# Motor_control.net
KiCad netlist of a schematic drawn in Altium Designer
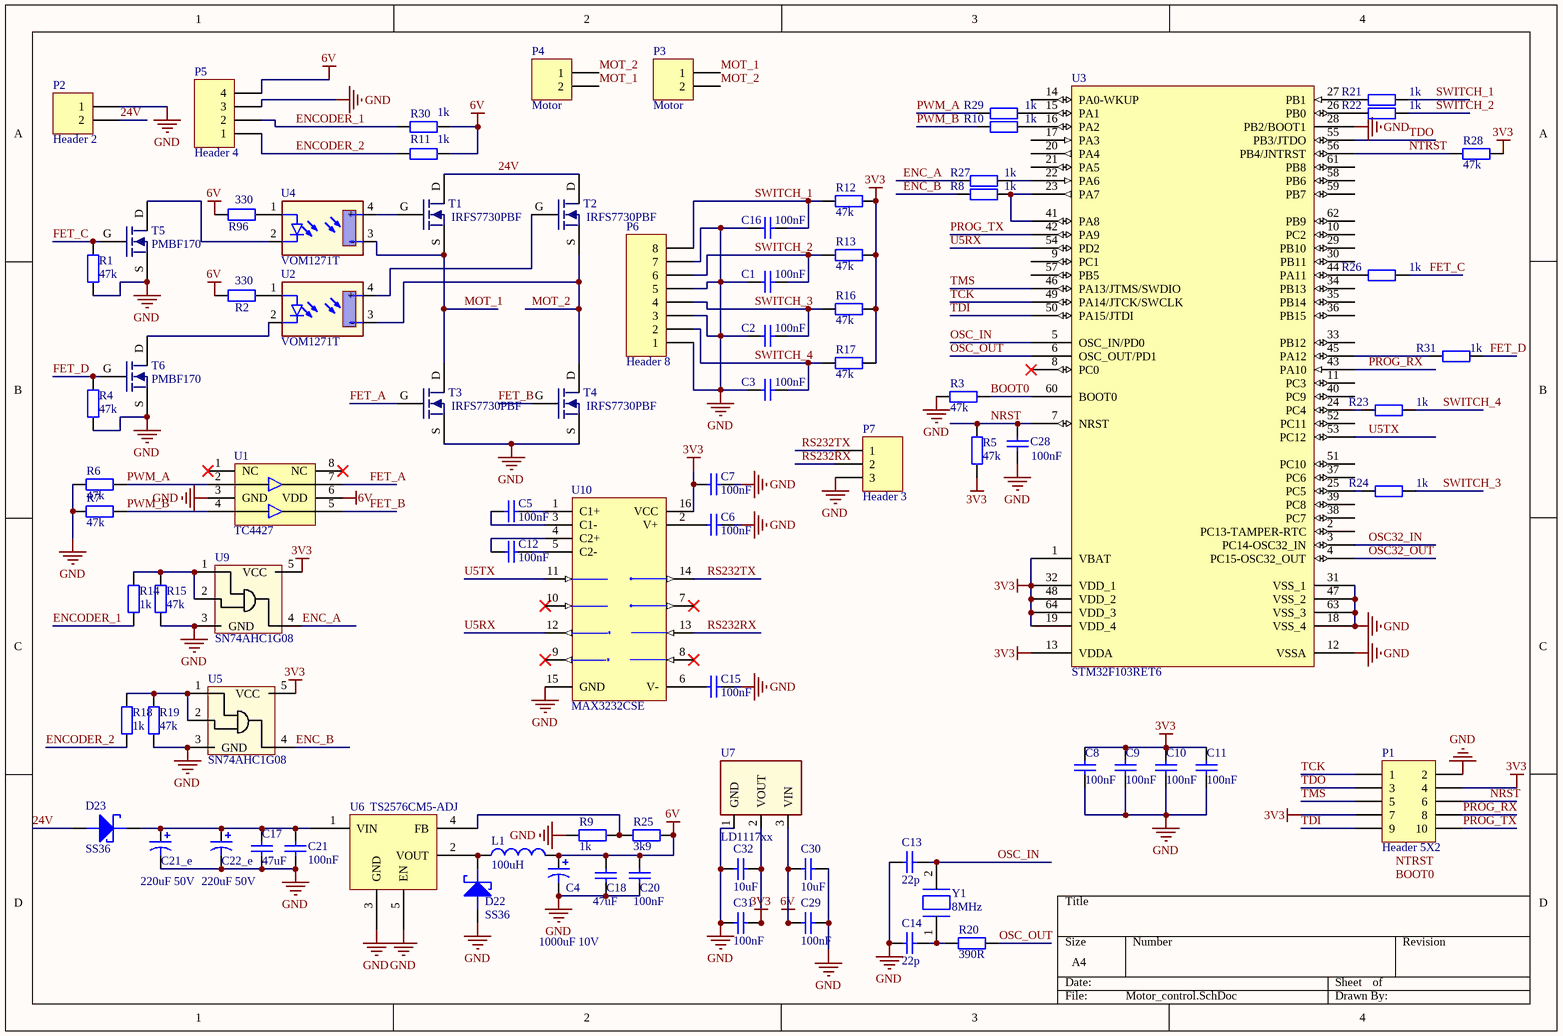
[diagram p0: Motor_control.SchDoc]

(export (version "E")
  (design (tool "Eeschema 10.0.6"))
  (components
    (comp (ref "C1")
      (value "100nF")
      (footprint "FP_0603_CAP_080")
      (description "Capacitor")
      (fields (field (name "VOLTAGE") "50V"))
      (libsource (lib "Miscellaneous Devices") (part "Cap"))
    )
    (comp (ref "C2")
      (value "100nF")
      (footprint "FP_0603_CAP_080")
      (description "Capacitor")
      (fields (field (name "VOLTAGE") "50V"))
      (libsource (lib "Miscellaneous Devices") (part "Cap"))
    )
    (comp (ref "C3")
      (value "100nF")
      (footprint "FP_0603_CAP_080")
      (description "Capacitor")
      (fields (field (name "VOLTAGE") "50V"))
      (libsource (lib "Miscellaneous Devices") (part "Cap"))
    )
    (comp (ref "C4")
      (value "1000uF 10V")
      (footprint "CAP_ALU_ELKO_10D_10,5H")
      (description "Polarized Capacitor (Radial)")
      (libsource (lib "Miscellaneous Devices") (part "Cap Pol1"))
    )
    (comp (ref "C5")
      (value "100nF")
      (footprint "FP_0603_CAP_080")
      (description "Capacitor")
      (libsource (lib "Capacitor") (part "CAP"))
    )
    (comp (ref "C6")
      (value "100nF")
      (footprint "FP_0603_CAP_080")
      (description "Capacitor")
      (libsource (lib "Capacitor") (part "CAP"))
    )
    (comp (ref "C7")
      (value "100nF")
      (footprint "FP_0603_CAP_080")
      (description "Capacitor")
      (libsource (lib "Capacitor") (part "CAP"))
    )
    (comp (ref "C8")
      (value "100nF")
      (footprint "FP_0603_CAP_080")
      (description "Capacitor")
      (libsource (lib "Capacitor") (part "CAP"))
    )
    (comp (ref "C9")
      (value "100nF")
      (footprint "FP_0603_CAP_080")
      (description "Capacitor")
      (libsource (lib "Capacitor") (part "CAP"))
    )
    (comp (ref "C10")
      (value "100nF")
      (footprint "FP_0603_CAP_080")
      (description "Capacitor")
      (libsource (lib "Capacitor") (part "CAP"))
    )
    (comp (ref "C11")
      (value "100nF")
      (footprint "FP_0603_CAP_080")
      (description "Capacitor")
      (libsource (lib "Capacitor") (part "CAP"))
    )
    (comp (ref "C12")
      (value "100nF")
      (footprint "FP_0603_CAP_080")
      (description "Capacitor")
      (libsource (lib "Capacitor") (part "CAP"))
    )
    (comp (ref "C13")
      (value "22p")
      (footprint "FP_0603_CAP_080")
      (description "Capacitor")
      (fields (field (name "PUBLISHER") "Altium Limited"))
      (libsource (lib "Miscellaneous Devices") (part "Cap"))
    )
    (comp (ref "C14")
      (value "22p")
      (footprint "FP_0603_CAP_080")
      (description "Capacitor")
      (fields (field (name "PUBLISHER") "Altium Limited"))
      (libsource (lib "Miscellaneous Devices") (part "Cap"))
    )
    (comp (ref "C15")
      (value "100nF")
      (footprint "FP_0603_CAP_080")
      (description "Capacitor")
      (libsource (lib "Capacitor") (part "CAP"))
    )
    (comp (ref "C16")
      (value "100nF")
      (footprint "FP_0603_CAP_080")
      (description "Capacitor")
      (fields (field (name "VOLTAGE") "50V"))
      (libsource (lib "Miscellaneous Devices") (part "Cap"))
    )
    (comp (ref "C17")
      (value "47uF")
      (footprint "FP_1206_CAP_125")
      (description "Capacitor")
      (libsource (lib "Miscellaneous Devices") (part "Cap"))
    )
    (comp (ref "C18")
      (value "47uF")
      (footprint "FP_1206_CAP_125")
      (description "Capacitor")
      (libsource (lib "Miscellaneous Devices") (part "Cap"))
    )
    (comp (ref "C20")
      (value "100nF")
      (footprint "FP_0603_CAP_080")
      (description "Capacitor")
      (libsource (lib "Miscellaneous Devices") (part "Cap"))
    )
    (comp (ref "C21")
      (value "100nF")
      (footprint "FP_0603_CAP_080")
      (description "Capacitor")
      (libsource (lib "Miscellaneous Devices") (part "Cap"))
    )
    (comp (ref "C21_e")
      (value "220uF 50V")
      (footprint "CAP_ALU_ELKO_10D_10,5H")
      (description "Polarized Capacitor (Radial)")
      (libsource (lib "Miscellaneous Devices") (part "Cap Pol1"))
    )
    (comp (ref "C22_e")
      (value "220uF 50V")
      (footprint "CAP_ALU_ELKO_10D_10,5H")
      (description "Polarized Capacitor (Radial)")
      (libsource (lib "Miscellaneous Devices") (part "Cap Pol1"))
    )
    (comp (ref "C28")
      (value "100nF")
      (footprint "FP_0603_CAP_080")
      (description "Capacitor")
      (libsource (lib "Miscellaneous Devices") (part "Cap"))
    )
    (comp (ref "C29")
      (value "100nF")
      (footprint "FP_0603_CAP_080")
      (description "Capacitor")
      (fields (field (name "PUBLISHER") "Altium Limited"))
      (libsource (lib "Miscellaneous Devices") (part "Cap"))
    )
    (comp (ref "C30")
      (value "10uF")
      (footprint "FP_1206_CAP_085")
      (description "Capacitor")
      (fields (field (name "PUBLISHER") "Altium Limited"))
      (libsource (lib "Miscellaneous Devices") (part "Cap"))
    )
    (comp (ref "C31")
      (value "100nF")
      (footprint "FP_0603_CAP_080")
      (description "Capacitor")
      (fields (field (name "PUBLISHER") "Altium Limited"))
      (libsource (lib "Miscellaneous Devices") (part "Cap"))
    )
    (comp (ref "C32")
      (value "10uF")
      (footprint "FP_1206_CAP_085")
      (description "Capacitor")
      (fields (field (name "PUBLISHER") "Altium Limited"))
      (libsource (lib "Miscellaneous Devices") (part "Cap"))
    )
    (comp (ref "D22")
      (value "SS36")
      (footprint "DIODE_SMC")
      (description "NXP - PMEG3020EJ,115 - SCHOTTKY RECT 30V 2A SOD323F")
      (libsource (lib "Diode") (part "SCHOTTKY"))
    )
    (comp (ref "D23")
      (value "SS36")
      (footprint "DIODE_SMC")
      (description "NXP - PMEG3020EJ,115 - SCHOTTKY RECT 30V 2A SOD323F")
      (libsource (lib "Diode") (part "SCHOTTKY"))
    )
    (comp (ref "L1")
      (value "100uH")
      (footprint "SRR1206_T")
      (description "Inductor")
      (fields (field (name "PUBLISHER") "Altium Limited"))
      (libsource (lib "Miscellaneous Devices") (part "Inductor"))
    )
    (comp (ref "P1")
      (value "Header 5X2")
      (footprint "HEADER_10_BOX")
      (description "Header, 5-Pin, Dual row")
      (fields (field (name "PUBLISHER") "Altium Limited"))
      (libsource (lib "EtherIOv2") (part "Header 5X2"))
    )
    (comp (ref "P2")
      (value "Header 2")
      (footprint "Sorkapocs 2P 5mm")
      (description "Header, 2-Pin")
      (libsource (lib "Miscellaneous Connectors") (part "Header 2"))
    )
    (comp (ref "P3")
      (value "Motor")
      (footprint "Sorkapocs 2P 5mm")
      (description "Header, 2-Pin")
      (libsource (lib "Miscellaneous Connectors") (part "Header 2"))
    )
    (comp (ref "P4")
      (value "Motor")
      (footprint "3.96mm 2P  90° NCW396-02R")
      (description "Header, 2-Pin")
      (libsource (lib "Miscellaneous Connectors") (part "Header 2"))
    )
    (comp (ref "P5")
      (value "Header 4")
      (footprint "jst-s4b-xh-a")
      (description "Header, 4-Pin")
      (libsource (lib "Miscellaneous Connectors") (part "Header 4"))
    )
    (comp (ref "P6")
      (value "Header 8")
      (footprint "Sorkapocs 8P 5mm")
      (description "Header, 8-Pin")
      (libsource (lib "Miscellaneous Connectors") (part "Header 8"))
    )
    (comp (ref "P7")
      (value "Header 3")
      (footprint "Sorkapocs 3P 5mm")
      (description "Header, 3-Pin")
      (libsource (lib "Miscellaneous Connectors") (part "Header 3"))
    )
    (comp (ref "R1")
      (value "47k")
      (footprint "FP_0603_RES")
      (description "Resistor")
      (libsource (lib "Miscellaneous Devices") (part "Res3"))
    )
    (comp (ref "R2")
      (value "330")
      (footprint "FP_0603_RES")
      (description "Resistor")
      (libsource (lib "") (part "Res3_2"))
    )
    (comp (ref "R3")
      (value "47k")
      (footprint "FP_0603_RES")
      (description "Resistor")
      (libsource (lib "") (part "Res3_1"))
    )
    (comp (ref "R4")
      (value "47k")
      (footprint "FP_0603_RES")
      (description "Resistor")
      (libsource (lib "Miscellaneous Devices") (part "Res3"))
    )
    (comp (ref "R5")
      (value "47k")
      (footprint "FP_0603_RES")
      (description "Resistor")
      (libsource (lib "Miscellaneous Devices") (part "Res3"))
    )
    (comp (ref "R6")
      (value "47k")
      (footprint "FP_0603_RES")
      (description "Resistor")
      (libsource (lib "") (part "Res3_1"))
    )
    (comp (ref "R7")
      (value "47k")
      (footprint "FP_0603_RES")
      (description "Resistor")
      (libsource (lib "") (part "Res3_1"))
    )
    (comp (ref "R8")
      (value "1k")
      (footprint "FP_0603_RES")
      (description "Resistor")
      (libsource (lib "") (part "Res3_1"))
    )
    (comp (ref "R9")
      (value "1k")
      (footprint "FP_0603_RES")
      (description "Resistor")
      (libsource (lib "") (part "Res3_1"))
    )
    (comp (ref "R10")
      (value "1k")
      (footprint "FP_0603_RES")
      (description "Resistor")
      (libsource (lib "") (part "Res3_1"))
    )
    (comp (ref "R11")
      (value "1k")
      (footprint "FP_0603_RES")
      (description "Resistor")
      (libsource (lib "") (part "Res3_1"))
    )
    (comp (ref "R12")
      (value "47k")
      (footprint "FP_0603_RES")
      (description "Resistor")
      (libsource (lib "") (part "Res3_1"))
    )
    (comp (ref "R13")
      (value "47k")
      (footprint "FP_0603_RES")
      (description "Resistor")
      (libsource (lib "") (part "Res3_1"))
    )
    (comp (ref "R14")
      (value "1k")
      (footprint "FP_0603_RES")
      (description "Resistor")
      (libsource (lib "Miscellaneous Devices") (part "Res3"))
    )
    (comp (ref "R15")
      (value "47k")
      (footprint "FP_0603_RES")
      (description "Resistor")
      (libsource (lib "Miscellaneous Devices") (part "Res3"))
    )
    (comp (ref "R16")
      (value "47k")
      (footprint "FP_0603_RES")
      (description "Resistor")
      (libsource (lib "") (part "Res3_1"))
    )
    (comp (ref "R17")
      (value "47k")
      (footprint "FP_0603_RES")
      (description "Resistor")
      (libsource (lib "") (part "Res3_1"))
    )
    (comp (ref "R18")
      (value "1k")
      (footprint "FP_0603_RES")
      (description "Resistor")
      (libsource (lib "Miscellaneous Devices") (part "Res3"))
    )
    (comp (ref "R19")
      (value "47k")
      (footprint "FP_0603_RES")
      (description "Resistor")
      (libsource (lib "Miscellaneous Devices") (part "Res3"))
    )
    (comp (ref "R20")
      (value "390R")
      (footprint "FP_0603_RES")
      (description "Resistor")
      (libsource (lib "Resistor") (part "RES"))
    )
    (comp (ref "R21")
      (value "1k")
      (footprint "FP_0603_RES")
      (description "Resistor")
      (libsource (lib "") (part "Res3_1"))
    )
    (comp (ref "R22")
      (value "1k")
      (footprint "FP_0603_RES")
      (description "Resistor")
      (libsource (lib "") (part "Res3_1"))
    )
    (comp (ref "R23")
      (value "1k")
      (footprint "FP_0603_RES")
      (description "Resistor")
      (libsource (lib "") (part "Res3_1"))
    )
    (comp (ref "R24")
      (value "1k")
      (footprint "FP_0603_RES")
      (description "Resistor")
      (libsource (lib "") (part "Res3_1"))
    )
    (comp (ref "R25")
      (value "3k9")
      (footprint "FP_0603_RES")
      (description "Resistor")
      (libsource (lib "") (part "Res3_2"))
    )
    (comp (ref "R26")
      (value "1k")
      (footprint "FP_0603_RES")
      (description "Resistor")
      (libsource (lib "") (part "Res3_1"))
    )
    (comp (ref "R27")
      (value "1k")
      (footprint "FP_0603_RES")
      (description "Resistor")
      (libsource (lib "") (part "Res3_1"))
    )
    (comp (ref "R28")
      (value "47k")
      (footprint "FP_0603_RES")
      (description "Resistor")
      (libsource (lib "") (part "Res3_1"))
    )
    (comp (ref "R29")
      (value "1k")
      (footprint "FP_0603_RES")
      (description "Resistor")
      (libsource (lib "") (part "Res3_1"))
    )
    (comp (ref "R30")
      (value "1k")
      (footprint "FP_0603_RES")
      (description "Resistor")
      (libsource (lib "") (part "Res3_1"))
    )
    (comp (ref "R31")
      (value "1k")
      (footprint "FP_0603_RES")
      (description "Resistor")
      (libsource (lib "") (part "Res3_1"))
    )
    (comp (ref "R96")
      (value "330")
      (footprint "FP_0603_RES")
      (description "Resistor")
      (libsource (lib "") (part "Res3_2"))
    )
    (comp (ref "T1") (value "IRFS7730PBF") (footprint "FET_D2-PAK_7") (libsource (lib "FET") (part "NMOS")))
    (comp (ref "T2") (value "IRFS7730PBF") (footprint "FET_D2-PAK_7") (libsource (lib "FET") (part "NMOS")))
    (comp (ref "T3") (value "IRFS7730PBF") (footprint "FET_D2-PAK_7") (libsource (lib "FET") (part "NMOS")))
    (comp (ref "T4") (value "IRFS7730PBF") (footprint "FET_D2-PAK_7") (libsource (lib "FET") (part "NMOS")))
    (comp (ref "T5") (value "PMBF170") (footprint "FET_SOT23") (libsource (lib "FET") (part "NMOS")))
    (comp (ref "T6") (value "PMBF170") (footprint "FET_SOT23") (libsource (lib "FET") (part "NMOS")))
    (comp (ref "U1")
      (value "TC4427")
      (footprint "DIGITAL_SOIC8")
      (description "1.5A Dual High-Speed Power MOSFET Driver")
      (libsource (lib "Analog") (part "TC4427"))
    )
    (comp (ref "U2")
      (value "VOM1271T")
      (footprint "OPTO_SOP-4")
      (description "Photodiode Output Optocouplers MOSFET DRVR ISOLATED SOP4")
      (libsource (lib "Led_optical") (part "VOM1271T"))
    )
    (comp (ref "U3")
      (value "STM32F103RET6")
      (footprint "LQFP64_N")
      (description "STM32 ARM-based 32-bit MCU with 256 Kbytes Flash, 64-pin LQFP, Industrial Temperature")
      (libsource (lib "ST Microcontroller 32-Bit STM32") (part "STM32F103RBT6"))
    )
    (comp (ref "U4")
      (value "VOM1271T")
      (footprint "OPTO_SOP-4")
      (description "Photodiode Output Optocouplers MOSFET DRVR ISOLATED SOP4")
      (libsource (lib "Led_optical") (part "VOM1271T"))
    )
    (comp (ref "U5")
      (value "SN74AHC1G08")
      (footprint "GATE_SOT23-5")
      (description "1x2-INPUT AND-GATE")
      (libsource (lib "Logic_gate") (part "SN74AHC1G08"))
    )
    (comp (ref "U6")
      (value "TS2576CM5-ADJ")
      (footprint "SUPPLY_TO-263 5")
      (description "Step Down DC-DC Converter")
      (libsource (lib "EtherIOv2") (part "TS2576"))
    )
    (comp (ref "U7")
      (value "LD1117xx")
      (footprint "SUPPLY_SOT223")
      (description "LD1117xx 3,3V lin reg")
      (libsource (lib "Supply") (part "LD1117xx"))
    )
    (comp (ref "U9")
      (value "SN74AHC1G08")
      (footprint "GATE_SOT23-5")
      (description "1x2-INPUT AND-GATE")
      (libsource (lib "Logic_gate") (part "SN74AHC1G08"))
    )
    (comp (ref "U10")
      (value "MAX3232CSE")
      (footprint "DIGITAL_SOIC16")
      (description "MAX3232CSE 3.3.V RS232 converter")
      (libsource (lib "Digital") (part "MAX3232CSE"))
    )
    (comp (ref "Y1")
      (value "8MHz")
      (footprint "FP_CRYSTAL_HC49_SMD")
      (description "Standard HC49 quartz")
      (fields (field (name "MANUFACTURER") "Siward") (field (name "Comment") "8MHz Quartz HC49"))
      (libsource (lib "Fufi_altium_lib") (part "XTAL HC49"))
    )
  )
  (nets
    (net (code "1") (name "/24V") (class "Default")
      (node (ref "D23") (pin "A") (pinfunction "A_A") (pintype "passive"))
      (node (ref "P2") (pin "2") (pinfunction "2_2") (pintype "passive"))
      (node (ref "T1") (pin "D") (pinfunction "D_D") (pintype "passive"))
      (node (ref "T2") (pin "D") (pinfunction "D_D") (pintype "passive"))
    )
    (net (code "2") (name "/BOOT0") (class "Default")
      (node (ref "R3") (pin "2") (pinfunction "2_2") (pintype "passive"))
      (node (ref "U3") (pin "60") (pinfunction "BOOT0_60") (pintype "passive"))
    )
    (net (code "3") (name "/ENCODER_1") (class "Default")
      (node (ref "P5") (pin "2") (pinfunction "2_2") (pintype "passive"))
      (node (ref "R14") (pin "2") (pinfunction "2_2") (pintype "passive"))
      (node (ref "R30") (pin "1") (pinfunction "1_1") (pintype "passive"))
    )
    (net (code "4") (name "/ENCODER_2") (class "Default")
      (node (ref "P5") (pin "1") (pinfunction "1_1") (pintype "passive"))
      (node (ref "R11") (pin "1") (pinfunction "1_1") (pintype "passive"))
      (node (ref "R18") (pin "2") (pinfunction "2_2") (pintype "passive"))
    )
    (net (code "5") (name "/ENC_A") (class "Default")
      (node (ref "R27") (pin "1") (pinfunction "1_1") (pintype "passive"))
      (node (ref "U9") (pin "4") (pinfunction "Y_4") (pintype "passive"))
    )
    (net (code "6") (name "/ENC_B") (class "Default")
      (node (ref "R8") (pin "1") (pinfunction "1_1") (pintype "passive"))
      (node (ref "U5") (pin "4") (pinfunction "Y_4") (pintype "passive"))
    )
    (net (code "7") (name "/FET_A") (class "Default")
      (node (ref "T3") (pin "G") (pinfunction "G_G") (pintype "passive"))
      (node (ref "U1") (pin "7") (pinfunction "~{OUTA}_7") (pintype "passive"))
    )
    (net (code "8") (name "/FET_B") (class "Default")
      (node (ref "T4") (pin "G") (pinfunction "G_G") (pintype "passive"))
      (node (ref "U1") (pin "5") (pinfunction "OUTB_5") (pintype "passive"))
    )
    (net (code "9") (name "/FET_C") (class "Default")
      (node (ref "R1") (pin "1") (pinfunction "1_1") (pintype "passive"))
      (node (ref "R26") (pin "2") (pinfunction "2_2") (pintype "passive"))
      (node (ref "T5") (pin "G") (pinfunction "G_G") (pintype "passive"))
    )
    (net (code "10") (name "/FET_D") (class "Default")
      (node (ref "R31") (pin "2") (pinfunction "2_2") (pintype "passive"))
      (node (ref "R4") (pin "1") (pinfunction "1_1") (pintype "passive"))
      (node (ref "T6") (pin "G") (pinfunction "G_G") (pintype "passive"))
    )
    (net (code "11") (name "/MOT_1") (class "Default")
      (node (ref "P3") (pin "1") (pinfunction "1_1") (pintype "passive"))
      (node (ref "P4") (pin "2") (pinfunction "2_2") (pintype "passive"))
      (node (ref "T1") (pin "S") (pinfunction "S_S") (pintype "passive"))
      (node (ref "T3") (pin "D") (pinfunction "D_D") (pintype "passive"))
      (node (ref "U4") (pin "3") (pinfunction "-_3") (pintype "passive"))
    )
    (net (code "12") (name "/MOT_2") (class "Default")
      (node (ref "P3") (pin "2") (pinfunction "2_2") (pintype "passive"))
      (node (ref "P4") (pin "1") (pinfunction "1_1") (pintype "passive"))
      (node (ref "T2") (pin "S") (pinfunction "S_S") (pintype "passive"))
      (node (ref "T4") (pin "D") (pinfunction "D_D") (pintype "passive"))
      (node (ref "U2") (pin "3") (pinfunction "-_3") (pintype "passive"))
    )
    (net (code "13") (name "/NRST") (class "Default")
      (node (ref "C28") (pin "1") (pinfunction "1_1") (pintype "passive"))
      (node (ref "P1") (pin "6") (pinfunction "6_6") (pintype "passive"))
      (node (ref "R5") (pin "1") (pinfunction "1_1") (pintype "passive"))
      (node (ref "U3") (pin "7") (pinfunction "NRST_7") (pintype "bidirectional"))
    )
    (net (code "14") (name "/NTRST") (class "Default")
      (node (ref "R28") (pin "1") (pinfunction "1_1") (pintype "passive"))
      (node (ref "U3") (pin "56") (pinfunction "PB4/JNTRST_56") (pintype "bidirectional"))
    )
    (net (code "15") (name "/OSC32_IN") (class "Default")
      (node (ref "U3") (pin "3") (pinfunction "PC14-OSC32_IN_3") (pintype "bidirectional"))
    )
    (net (code "16") (name "/OSC32_OUT") (class "Default")
      (node (ref "U3") (pin "4") (pinfunction "PC15-OSC32_OUT_4") (pintype "bidirectional"))
    )
    (net (code "17") (name "/OSC_IN") (class "Default")
      (node (ref "C13") (pin "2") (pinfunction "2_2") (pintype "passive"))
      (node (ref "U3") (pin "5") (pinfunction "OSC_IN/PD0_5") (pintype "passive"))
      (node (ref "Y1") (pin "2") (pinfunction "2_2") (pintype "passive"))
    )
    (net (code "18") (name "/OSC_OUT") (class "Default")
      (node (ref "R20") (pin "2") (pinfunction "2_2") (pintype "passive"))
      (node (ref "U3") (pin "6") (pinfunction "OSC_OUT/PD1_6") (pintype "passive"))
    )
    (net (code "19") (name "/PROG_RX") (class "Default")
      (node (ref "P1") (pin "8") (pinfunction "8_8") (pintype "passive"))
      (node (ref "U3") (pin "43") (pinfunction "PA10_43") (pintype "input"))
    )
    (net (code "20") (name "/PROG_TX") (class "Default")
      (node (ref "P1") (pin "10") (pinfunction "10_10") (pintype "passive"))
      (node (ref "U3") (pin "42") (pinfunction "PA9_42") (pintype "bidirectional"))
    )
    (net (code "21") (name "/PWM_A") (class "Default")
      (node (ref "R29") (pin "1") (pinfunction "1_1") (pintype "passive"))
      (node (ref "R6") (pin "2") (pinfunction "2_2") (pintype "passive"))
      (node (ref "U1") (pin "2") (pinfunction "INA_2") (pintype "passive"))
    )
    (net (code "22") (name "/PWM_B") (class "Default")
      (node (ref "R10") (pin "1") (pinfunction "1_1") (pintype "passive"))
      (node (ref "R7") (pin "2") (pinfunction "2_2") (pintype "passive"))
      (node (ref "U1") (pin "4") (pinfunction "INB_4") (pintype "passive"))
    )
    (net (code "23") (name "/RS232RX") (class "Default")
      (node (ref "P7") (pin "2") (pinfunction "2_2") (pintype "passive"))
      (node (ref "U10") (pin "13") (pinfunction "R1IN_13") (pintype "input"))
    )
    (net (code "24") (name "/RS232TX") (class "Default")
      (node (ref "P7") (pin "1") (pinfunction "1_1") (pintype "passive"))
      (node (ref "U10") (pin "14") (pinfunction "T1OUT_14") (pintype "output"))
    )
    (net (code "25") (name "/SWITCH_1") (class "Default")
      (node (ref "C16") (pin "2") (pinfunction "2_2") (pintype "passive"))
      (node (ref "P6") (pin "8") (pinfunction "8_8") (pintype "passive"))
      (node (ref "R12") (pin "1") (pinfunction "1_1") (pintype "passive"))
      (node (ref "R21") (pin "2") (pinfunction "2_2") (pintype "passive"))
    )
    (net (code "26") (name "/SWITCH_2") (class "Default")
      (node (ref "C1") (pin "2") (pinfunction "2_2") (pintype "passive"))
      (node (ref "P6") (pin "6") (pinfunction "6_6") (pintype "passive"))
      (node (ref "R13") (pin "1") (pinfunction "1_1") (pintype "passive"))
      (node (ref "R22") (pin "2") (pinfunction "2_2") (pintype "passive"))
    )
    (net (code "27") (name "/SWITCH_3") (class "Default")
      (node (ref "C2") (pin "2") (pinfunction "2_2") (pintype "passive"))
      (node (ref "P6") (pin "4") (pinfunction "4_4") (pintype "passive"))
      (node (ref "R16") (pin "1") (pinfunction "1_1") (pintype "passive"))
      (node (ref "R24") (pin "2") (pinfunction "2_2") (pintype "passive"))
    )
    (net (code "28") (name "/SWITCH_4") (class "Default")
      (node (ref "C3") (pin "2") (pinfunction "2_2") (pintype "passive"))
      (node (ref "P6") (pin "2") (pinfunction "2_2") (pintype "passive"))
      (node (ref "R17") (pin "1") (pinfunction "1_1") (pintype "passive"))
      (node (ref "R23") (pin "2") (pinfunction "2_2") (pintype "passive"))
    )
    (net (code "29") (name "/TCK") (class "Default")
      (node (ref "P1") (pin "1") (pinfunction "1_1") (pintype "passive"))
      (node (ref "U3") (pin "49") (pinfunction "PA14/JTCK/SWCLK_49") (pintype "bidirectional"))
    )
    (net (code "30") (name "/TDI") (class "Default")
      (node (ref "P1") (pin "9") (pinfunction "9_9") (pintype "passive"))
      (node (ref "U3") (pin "50") (pinfunction "PA15/JTDI_50") (pintype "bidirectional"))
    )
    (net (code "31") (name "/TDO") (class "Default")
      (node (ref "P1") (pin "3") (pinfunction "3_3") (pintype "passive"))
      (node (ref "U3") (pin "55") (pinfunction "PB3/JTDO_55") (pintype "bidirectional"))
    )
    (net (code "32") (name "/TMS") (class "Default")
      (node (ref "P1") (pin "5") (pinfunction "5_5") (pintype "passive"))
      (node (ref "U3") (pin "46") (pinfunction "PA13/JTMS/SWDIO_46") (pintype "bidirectional"))
    )
    (net (code "33") (name "/U5RX") (class "Default")
      (node (ref "U10") (pin "12") (pinfunction "R1OUT_12") (pintype "output"))
      (node (ref "U3") (pin "54") (pinfunction "PD2_54") (pintype "bidirectional"))
    )
    (net (code "34") (name "/U5TX") (class "Default")
      (node (ref "U10") (pin "11") (pinfunction "T1IN_11") (pintype "input"))
      (node (ref "U3") (pin "53") (pinfunction "PC12_53") (pintype "bidirectional"))
    )
    (net (code "35") (name "3V3") (class "Default")
      (node (ref "C10") (pin "2") (pinfunction "2_2") (pintype "passive"))
      (node (ref "C11") (pin "2") (pinfunction "2_2") (pintype "passive"))
      (node (ref "C31") (pin "1") (pinfunction "1_1") (pintype "passive"))
      (node (ref "C32") (pin "2") (pinfunction "2_2") (pintype "passive"))
      (node (ref "C7") (pin "2") (pinfunction "2_2") (pintype "passive"))
      (node (ref "C8") (pin "2") (pinfunction "2_2") (pintype "passive"))
      (node (ref "C9") (pin "2") (pinfunction "2_2") (pintype "passive"))
      (node (ref "P1") (pin "4") (pinfunction "4_4") (pintype "passive"))
      (node (ref "P1") (pin "7") (pinfunction "7_7") (pintype "passive"))
      (node (ref "R12") (pin "2") (pinfunction "2_2") (pintype "passive"))
      (node (ref "R13") (pin "2") (pinfunction "2_2") (pintype "passive"))
      (node (ref "R16") (pin "2") (pinfunction "2_2") (pintype "passive"))
      (node (ref "R17") (pin "2") (pinfunction "2_2") (pintype "passive"))
      (node (ref "R28") (pin "2") (pinfunction "2_2") (pintype "passive"))
      (node (ref "R5") (pin "2") (pinfunction "2_2") (pintype "passive"))
      (node (ref "U10") (pin "16") (pinfunction "VCC_16") (pintype "power_in"))
      (node (ref "U3") (pin "1") (pinfunction "VBAT_1") (pintype "power_in"))
      (node (ref "U3") (pin "13") (pinfunction "VDDA_13") (pintype "power_in"))
      (node (ref "U3") (pin "19") (pinfunction "VDD_4_19") (pintype "power_in"))
      (node (ref "U3") (pin "32") (pinfunction "VDD_1_32") (pintype "power_in"))
      (node (ref "U3") (pin "48") (pinfunction "VDD_2_48") (pintype "power_in"))
      (node (ref "U3") (pin "64") (pinfunction "VDD_3_64") (pintype "power_in"))
      (node (ref "U5") (pin "5") (pinfunction "VCC_5") (pintype "passive"))
      (node (ref "U7") (pin "2") (pinfunction "VOUT_2") (pintype "passive"))
      (node (ref "U9") (pin "5") (pinfunction "VCC_5") (pintype "passive"))
    )
    (net (code "36") (name "6V") (class "Default")
      (node (ref "C18") (pin "2") (pinfunction "2_2") (pintype "passive"))
      (node (ref "C20") (pin "1") (pinfunction "1_1") (pintype "passive"))
      (node (ref "C29") (pin "2") (pinfunction "2_2") (pintype "passive"))
      (node (ref "C30") (pin "1") (pinfunction "1_1") (pintype "passive"))
      (node (ref "C4") (pin "P") (pinfunction "1_P") (pintype "passive"))
      (node (ref "L1") (pin "2") (pinfunction "2_2") (pintype "passive"))
      (node (ref "P5") (pin "4") (pinfunction "4_4") (pintype "passive"))
      (node (ref "R11") (pin "2") (pinfunction "2_2") (pintype "passive"))
      (node (ref "R2") (pin "2") (pinfunction "2_2") (pintype "passive"))
      (node (ref "R25") (pin "1") (pinfunction "1_1") (pintype "passive"))
      (node (ref "R30") (pin "2") (pinfunction "2_2") (pintype "passive"))
      (node (ref "R96") (pin "2") (pinfunction "2_2") (pintype "passive"))
      (node (ref "U1") (pin "6") (pinfunction "VDD_6") (pintype "power_in"))
      (node (ref "U7") (pin "3") (pinfunction "VIN_3") (pintype "passive"))
    )
    (net (code "37") (name "GND") (class "Default")
      (node (ref "C1") (pin "1") (pinfunction "1_1") (pintype "passive"))
      (node (ref "C10") (pin "1") (pinfunction "1_1") (pintype "passive"))
      (node (ref "C11") (pin "1") (pinfunction "1_1") (pintype "passive"))
      (node (ref "C13") (pin "1") (pinfunction "1_1") (pintype "passive"))
      (node (ref "C14") (pin "2") (pinfunction "2_2") (pintype "passive"))
      (node (ref "C15") (pin "1") (pinfunction "1_1") (pintype "passive"))
      (node (ref "C16") (pin "1") (pinfunction "1_1") (pintype "passive"))
      (node (ref "C17") (pin "1") (pinfunction "1_1") (pintype "passive"))
      (node (ref "C18") (pin "1") (pinfunction "1_1") (pintype "passive"))
      (node (ref "C2") (pin "1") (pinfunction "1_1") (pintype "passive"))
      (node (ref "C20") (pin "2") (pinfunction "2_2") (pintype "passive"))
      (node (ref "C21") (pin "2") (pinfunction "2_2") (pintype "passive"))
      (node (ref "C21_e") (pin "N") (pinfunction "2_N") (pintype "passive"))
      (node (ref "C22_e") (pin "N") (pinfunction "2_N") (pintype "passive"))
      (node (ref "C28") (pin "2") (pinfunction "2_2") (pintype "passive"))
      (node (ref "C29") (pin "1") (pinfunction "1_1") (pintype "passive"))
      (node (ref "C3") (pin "1") (pinfunction "1_1") (pintype "passive"))
      (node (ref "C30") (pin "2") (pinfunction "2_2") (pintype "passive"))
      (node (ref "C31") (pin "2") (pinfunction "2_2") (pintype "passive"))
      (node (ref "C32") (pin "1") (pinfunction "1_1") (pintype "passive"))
      (node (ref "C4") (pin "N") (pinfunction "2_N") (pintype "passive"))
      (node (ref "C6") (pin "1") (pinfunction "1_1") (pintype "passive"))
      (node (ref "C7") (pin "1") (pinfunction "1_1") (pintype "passive"))
      (node (ref "C8") (pin "1") (pinfunction "1_1") (pintype "passive"))
      (node (ref "C9") (pin "1") (pinfunction "1_1") (pintype "passive"))
      (node (ref "D22") (pin "A") (pinfunction "A_A") (pintype "passive"))
      (node (ref "P1") (pin "2") (pinfunction "2_2") (pintype "passive"))
      (node (ref "P2") (pin "1") (pinfunction "1_1") (pintype "passive"))
      (node (ref "P5") (pin "3") (pinfunction "3_3") (pintype "passive"))
      (node (ref "P6") (pin "1") (pinfunction "1_1") (pintype "passive"))
      (node (ref "P6") (pin "3") (pinfunction "3_3") (pintype "passive"))
      (node (ref "P6") (pin "5") (pinfunction "5_5") (pintype "passive"))
      (node (ref "P6") (pin "7") (pinfunction "7_7") (pintype "passive"))
      (node (ref "P7") (pin "3") (pinfunction "3_3") (pintype "passive"))
      (node (ref "R1") (pin "2") (pinfunction "2_2") (pintype "passive"))
      (node (ref "R15") (pin "2") (pinfunction "2_2") (pintype "passive"))
      (node (ref "R19") (pin "2") (pinfunction "2_2") (pintype "passive"))
      (node (ref "R3") (pin "1") (pinfunction "1_1") (pintype "passive"))
      (node (ref "R4") (pin "2") (pinfunction "2_2") (pintype "passive"))
      (node (ref "R6") (pin "1") (pinfunction "1_1") (pintype "passive"))
      (node (ref "R7") (pin "1") (pinfunction "1_1") (pintype "passive"))
      (node (ref "R9") (pin "1") (pinfunction "1_1") (pintype "passive"))
      (node (ref "T3") (pin "S") (pinfunction "S_S") (pintype "passive"))
      (node (ref "T4") (pin "S") (pinfunction "S_S") (pintype "passive"))
      (node (ref "T5") (pin "S") (pinfunction "S_S") (pintype "passive"))
      (node (ref "T6") (pin "S") (pinfunction "S_S") (pintype "passive"))
      (node (ref "U1") (pin "3") (pinfunction "GND_3") (pintype "power_in"))
      (node (ref "U10") (pin "15") (pinfunction "GND_15") (pintype "power_in"))
      (node (ref "U3") (pin "12") (pinfunction "VSSA_12") (pintype "power_in"))
      (node (ref "U3") (pin "18") (pinfunction "VSS_4_18") (pintype "power_in"))
      (node (ref "U3") (pin "28") (pinfunction "PB2/BOOT1_28") (pintype "passive"))
      (node (ref "U3") (pin "31") (pinfunction "VSS_1_31") (pintype "power_in"))
      (node (ref "U3") (pin "47") (pinfunction "VSS_2_47") (pintype "power_in"))
      (node (ref "U3") (pin "63") (pinfunction "VSS_3_63") (pintype "power_in"))
      (node (ref "U5") (pin "3") (pinfunction "GND_3") (pintype "passive"))
      (node (ref "U6") (pin "3") (pinfunction "GND_3") (pintype "power_in"))
      (node (ref "U6") (pin "5") (pinfunction "EN_5") (pintype "passive"))
      (node (ref "U7") (pin "1") (pinfunction "GND_1") (pintype "passive"))
      (node (ref "U9") (pin "3") (pinfunction "GND_3") (pintype "passive"))
    )
    (net (code "38") (name "Net-(C14-Pad1)") (class "Default")
      (node (ref "C14") (pin "1") (pinfunction "1_1") (pintype "passive"))
      (node (ref "R20") (pin "1") (pinfunction "1_1") (pintype "passive"))
      (node (ref "Y1") (pin "1") (pinfunction "1_1") (pintype "passive"))
    )
    (net (code "39") (name "Net-(C21_e-1)") (class "Default")
      (node (ref "C17") (pin "2") (pinfunction "2_2") (pintype "passive"))
      (node (ref "C21") (pin "1") (pinfunction "1_1") (pintype "passive"))
      (node (ref "C21_e") (pin "P") (pinfunction "1_P") (pintype "passive"))
      (node (ref "C22_e") (pin "P") (pinfunction "1_P") (pintype "passive"))
      (node (ref "D23") (pin "K") (pinfunction "K_K") (pintype "passive"))
      (node (ref "U6") (pin "1") (pinfunction "VIN_1") (pintype "power_in"))
    )
    (net (code "40") (name "Net-(U2-+)") (class "Default")
      (node (ref "T2") (pin "G") (pinfunction "G_G") (pintype "passive"))
      (node (ref "U2") (pin "4") (pinfunction "+_4") (pintype "passive"))
    )
    (net (code "41") (name "Net-(U2-A)") (class "Default")
      (node (ref "R2") (pin "1") (pinfunction "1_1") (pintype "passive"))
      (node (ref "U2") (pin "1") (pinfunction "A_1") (pintype "passive"))
    )
    (net (code "42") (name "Net-(U2-K)") (class "Default")
      (node (ref "T6") (pin "D") (pinfunction "D_D") (pintype "passive"))
      (node (ref "U2") (pin "2") (pinfunction "K_2") (pintype "passive"))
    )
    (net (code "43") (name "Net-(U3-PA1)") (class "Default")
      (node (ref "R29") (pin "2") (pinfunction "2_2") (pintype "passive"))
      (node (ref "U3") (pin "15") (pinfunction "PA1_15") (pintype "bidirectional"))
    )
    (net (code "44") (name "Net-(U3-PA2)") (class "Default")
      (node (ref "R10") (pin "2") (pinfunction "2_2") (pintype "passive"))
      (node (ref "U3") (pin "16") (pinfunction "PA2_16") (pintype "bidirectional"))
    )
    (net (code "45") (name "Net-(U3-PA6)") (class "Default")
      (node (ref "R27") (pin "2") (pinfunction "2_2") (pintype "passive"))
      (node (ref "U3") (pin "22") (pinfunction "PA6_22") (pintype "input"))
    )
    (net (code "46") (name "Net-(U3-PA7)") (class "Default")
      (node (ref "R8") (pin "2") (pinfunction "2_2") (pintype "passive"))
      (node (ref "U3") (pin "23") (pinfunction "PA7_23") (pintype "output"))
      (node (ref "U3") (pin "41") (pinfunction "PA8_41") (pintype "bidirectional"))
    )
    (net (code "47") (name "Net-(U3-PA11)") (class "Default")
      (node (ref "R26") (pin "1") (pinfunction "1_1") (pintype "passive"))
      (node (ref "U3") (pin "44") (pinfunction "PA11_44") (pintype "bidirectional"))
    )
    (net (code "48") (name "Net-(U3-PA12)") (class "Default")
      (node (ref "R31") (pin "1") (pinfunction "1_1") (pintype "passive"))
      (node (ref "U3") (pin "45") (pinfunction "PA12_45") (pintype "bidirectional"))
    )
    (net (code "49") (name "Net-(U3-PB0)") (class "Default")
      (node (ref "R22") (pin "1") (pinfunction "1_1") (pintype "passive"))
      (node (ref "U3") (pin "26") (pinfunction "PB0_26") (pintype "bidirectional"))
    )
    (net (code "50") (name "Net-(U3-PB1)") (class "Default")
      (node (ref "R21") (pin "1") (pinfunction "1_1") (pintype "passive"))
      (node (ref "U3") (pin "27") (pinfunction "PB1_27") (pintype "input"))
    )
    (net (code "51") (name "Net-(U3-PC4)") (class "Default")
      (node (ref "R23") (pin "1") (pinfunction "1_1") (pintype "passive"))
      (node (ref "U3") (pin "24") (pinfunction "PC4_24") (pintype "bidirectional"))
    )
    (net (code "52") (name "Net-(U3-PC5)") (class "Default")
      (node (ref "R24") (pin "1") (pinfunction "1_1") (pintype "passive"))
      (node (ref "U3") (pin "25") (pinfunction "PC5_25") (pintype "bidirectional"))
    )
    (net (code "53") (name "Net-(U4-+)") (class "Default")
      (node (ref "T1") (pin "G") (pinfunction "G_G") (pintype "passive"))
      (node (ref "U4") (pin "4") (pinfunction "+_4") (pintype "passive"))
    )
    (net (code "54") (name "Net-(U4-A)") (class "Default")
      (node (ref "R96") (pin "1") (pinfunction "1_1") (pintype "passive"))
      (node (ref "U4") (pin "1") (pinfunction "A_1") (pintype "passive"))
    )
    (net (code "55") (name "Net-(U4-K)") (class "Default")
      (node (ref "T5") (pin "D") (pinfunction "D_D") (pintype "passive"))
      (node (ref "U4") (pin "2") (pinfunction "K_2") (pintype "passive"))
    )
    (net (code "56") (name "Net-(U5-A)") (class "Default")
      (node (ref "R18") (pin "1") (pinfunction "1_1") (pintype "passive"))
      (node (ref "R19") (pin "1") (pinfunction "1_1") (pintype "passive"))
      (node (ref "U5") (pin "1") (pinfunction "A_1") (pintype "passive"))
      (node (ref "U5") (pin "2") (pinfunction "B_2") (pintype "passive"))
    )
    (net (code "57") (name "Net-(U6-FB)") (class "Default")
      (node (ref "R25") (pin "2") (pinfunction "2_2") (pintype "passive"))
      (node (ref "R9") (pin "2") (pinfunction "2_2") (pintype "passive"))
      (node (ref "U6") (pin "4") (pinfunction "FB_4") (pintype "passive"))
    )
    (net (code "58") (name "Net-(U6-VOUT)") (class "Default")
      (node (ref "D22") (pin "K") (pinfunction "K_K") (pintype "passive"))
      (node (ref "L1") (pin "1") (pinfunction "1_1") (pintype "passive"))
      (node (ref "U6") (pin "2") (pinfunction "VOUT_2") (pintype "passive"))
    )
    (net (code "59") (name "Net-(U9-A)") (class "Default")
      (node (ref "R14") (pin "1") (pinfunction "1_1") (pintype "passive"))
      (node (ref "R15") (pin "1") (pinfunction "1_1") (pintype "passive"))
      (node (ref "U9") (pin "1") (pinfunction "A_1") (pintype "passive"))
      (node (ref "U9") (pin "2") (pinfunction "B_2") (pintype "passive"))
    )
    (net (code "60") (name "Net-(U10-C1+)") (class "Default")
      (node (ref "C5") (pin "1") (pinfunction "1_1") (pintype "passive"))
      (node (ref "U10") (pin "1") (pinfunction "C1+_1") (pintype "passive"))
    )
    (net (code "61") (name "Net-(U10-C1-)") (class "Default")
      (node (ref "C5") (pin "2") (pinfunction "2_2") (pintype "passive"))
      (node (ref "U10") (pin "3") (pinfunction "C1-_3") (pintype "passive"))
    )
    (net (code "62") (name "Net-(U10-C2+)") (class "Default")
      (node (ref "C12") (pin "2") (pinfunction "2_2") (pintype "passive"))
      (node (ref "U10") (pin "4") (pinfunction "C2+_4") (pintype "passive"))
    )
    (net (code "63") (name "Net-(U10-C2-)") (class "Default")
      (node (ref "C12") (pin "1") (pinfunction "1_1") (pintype "passive"))
      (node (ref "U10") (pin "5") (pinfunction "C2-_5") (pintype "passive"))
    )
    (net (code "64") (name "Net-(U10-V+)") (class "Default")
      (node (ref "C6") (pin "2") (pinfunction "2_2") (pintype "passive"))
      (node (ref "U10") (pin "2") (pinfunction "V+_2") (pintype "power_in"))
    )
    (net (code "65") (name "Net-(U10-V-)") (class "Default")
      (node (ref "C15") (pin "2") (pinfunction "2_2") (pintype "passive"))
      (node (ref "U10") (pin "6") (pinfunction "V-_6") (pintype "power_in"))
    )
    (net (code "66") (name "unconnected-(U1-NC-Pad1)") (class "Default")
      (node (ref "U1") (pin "1") (pinfunction "NC_1") (pintype "passive+no_connect"))
    )
    (net (code "67") (name "unconnected-(U1-NC-Pad8)") (class "Default")
      (node (ref "U1") (pin "8") (pinfunction "NC_8") (pintype "passive+no_connect"))
    )
    (net (code "68") (name "unconnected-(U3-PA0-WKUP-Pad14)") (class "Default")
      (node (ref "U3") (pin "14") (pinfunction "PA0-WKUP_14") (pintype "bidirectional"))
    )
    (net (code "69") (name "unconnected-(U3-PA3-Pad17)") (class "Default")
      (node (ref "U3") (pin "17") (pinfunction "PA3_17") (pintype "input"))
    )
    (net (code "70") (name "unconnected-(U3-PA4-Pad20)") (class "Default")
      (node (ref "U3") (pin "20") (pinfunction "PA4_20") (pintype "output"))
    )
    (net (code "71") (name "unconnected-(U3-PA5-Pad21)") (class "Default")
      (node (ref "U3") (pin "21") (pinfunction "PA5_21") (pintype "bidirectional"))
    )
    (net (code "72") (name "unconnected-(U3-PB5-Pad57)") (class "Default")
      (node (ref "U3") (pin "57") (pinfunction "PB5_57") (pintype "bidirectional"))
    )
    (net (code "73") (name "unconnected-(U3-PB6-Pad58)") (class "Default")
      (node (ref "U3") (pin "58") (pinfunction "PB6_58") (pintype "bidirectional"))
    )
    (net (code "74") (name "unconnected-(U3-PB7-Pad59)") (class "Default")
      (node (ref "U3") (pin "59") (pinfunction "PB7_59") (pintype "bidirectional"))
    )
    (net (code "75") (name "unconnected-(U3-PB8-Pad61)") (class "Default")
      (node (ref "U3") (pin "61") (pinfunction "PB8_61") (pintype "bidirectional"))
    )
    (net (code "76") (name "unconnected-(U3-PB9-Pad62)") (class "Default")
      (node (ref "U3") (pin "62") (pinfunction "PB9_62") (pintype "bidirectional"))
    )
    (net (code "77") (name "unconnected-(U3-PB10-Pad29)") (class "Default")
      (node (ref "U3") (pin "29") (pinfunction "PB10_29") (pintype "bidirectional"))
    )
    (net (code "78") (name "unconnected-(U3-PB11-Pad30)") (class "Default")
      (node (ref "U3") (pin "30") (pinfunction "PB11_30") (pintype "bidirectional"))
    )
    (net (code "79") (name "unconnected-(U3-PB12-Pad33)") (class "Default")
      (node (ref "U3") (pin "33") (pinfunction "PB12_33") (pintype "bidirectional"))
    )
    (net (code "80") (name "unconnected-(U3-PB13-Pad34)") (class "Default")
      (node (ref "U3") (pin "34") (pinfunction "PB13_34") (pintype "bidirectional"))
    )
    (net (code "81") (name "unconnected-(U3-PB14-Pad35)") (class "Default")
      (node (ref "U3") (pin "35") (pinfunction "PB14_35") (pintype "bidirectional"))
    )
    (net (code "82") (name "unconnected-(U3-PB15-Pad36)") (class "Default")
      (node (ref "U3") (pin "36") (pinfunction "PB15_36") (pintype "bidirectional"))
    )
    (net (code "83") (name "unconnected-(U3-PC0-Pad8)") (class "Default")
      (node (ref "U3") (pin "8") (pinfunction "PC0_8") (pintype "bidirectional+no_connect"))
    )
    (net (code "84") (name "unconnected-(U3-PC1-Pad9)") (class "Default")
      (node (ref "U3") (pin "9") (pinfunction "PC1_9") (pintype "bidirectional"))
    )
    (net (code "85") (name "unconnected-(U3-PC2-Pad10)") (class "Default")
      (node (ref "U3") (pin "10") (pinfunction "PC2_10") (pintype "bidirectional"))
    )
    (net (code "86") (name "unconnected-(U3-PC3-Pad11)") (class "Default")
      (node (ref "U3") (pin "11") (pinfunction "PC3_11") (pintype "bidirectional"))
    )
    (net (code "87") (name "unconnected-(U3-PC6-Pad37)") (class "Default")
      (node (ref "U3") (pin "37") (pinfunction "PC6_37") (pintype "bidirectional"))
    )
    (net (code "88") (name "unconnected-(U3-PC7-Pad38)") (class "Default")
      (node (ref "U3") (pin "38") (pinfunction "PC7_38") (pintype "bidirectional"))
    )
    (net (code "89") (name "unconnected-(U3-PC8-Pad39)") (class "Default")
      (node (ref "U3") (pin "39") (pinfunction "PC8_39") (pintype "bidirectional"))
    )
    (net (code "90") (name "unconnected-(U3-PC9-Pad40)") (class "Default")
      (node (ref "U3") (pin "40") (pinfunction "PC9_40") (pintype "bidirectional"))
    )
    (net (code "91") (name "unconnected-(U3-PC10-Pad51)") (class "Default")
      (node (ref "U3") (pin "51") (pinfunction "PC10_51") (pintype "bidirectional"))
    )
    (net (code "92") (name "unconnected-(U3-PC11-Pad52)") (class "Default")
      (node (ref "U3") (pin "52") (pinfunction "PC11_52") (pintype "bidirectional"))
    )
    (net (code "93") (name "unconnected-(U3-PC13-TAMPER-RTC-Pad2)") (class "Default")
      (node (ref "U3") (pin "2") (pinfunction "PC13-TAMPER-RTC_2") (pintype "bidirectional"))
    )
    (net (code "94") (name "unconnected-(U10-R2IN-Pad8)") (class "Default")
      (node (ref "U10") (pin "8") (pinfunction "R2IN_8") (pintype "input+no_connect"))
    )
    (net (code "95") (name "unconnected-(U10-R2OUT-Pad9)") (class "Default")
      (node (ref "U10") (pin "9") (pinfunction "R2OUT_9") (pintype "output+no_connect"))
    )
    (net (code "96") (name "unconnected-(U10-T2IN-Pad10)") (class "Default")
      (node (ref "U10") (pin "10") (pinfunction "T2IN_10") (pintype "input+no_connect"))
    )
    (net (code "97") (name "unconnected-(U10-T2OUT-Pad7)") (class "Default")
      (node (ref "U10") (pin "7") (pinfunction "T2OUT_7") (pintype "output+no_connect"))
    )
  )
)
